# User_Interface.net
KiCad netlist of a schematic drawn in Altium Designer
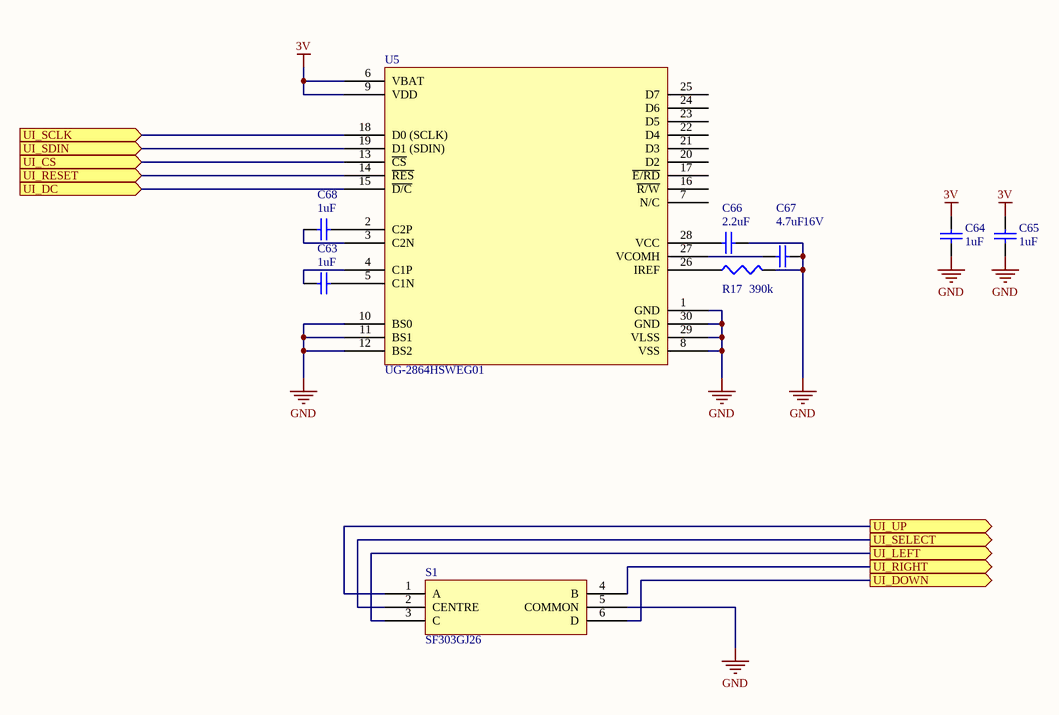
[diagram p0: User_Interface.SchDoc]

(export (version "E")
  (design (tool "Eeschema 10.0.6"))
  (components
    (comp (ref "C63")
      (value "1uF")
      (footprint "1608[0603]")
      (description "Capacitor (Semiconductor SIM Model)")
      (fields (field (name "Comment") "Cap Semi") (field (name "PUBLISHER") "Altium Limited"))
      (libsource (lib "Miscellaneous Devices") (part "Cap Semi"))
    )
    (comp (ref "C64")
      (value "1uF")
      (footprint "1608[0603]")
      (description "Capacitor (Semiconductor SIM Model)")
      (fields (field (name "Comment") "Cap Semi") (field (name "PUBLISHER") "Altium Limited"))
      (libsource (lib "Miscellaneous Devices") (part "Cap Semi"))
    )
    (comp (ref "C65")
      (value "1uF")
      (footprint "1608[0603]")
      (description "Capacitor (Semiconductor SIM Model)")
      (fields (field (name "Comment") "Cap Semi") (field (name "PUBLISHER") "Altium Limited"))
      (libsource (lib "Miscellaneous Devices") (part "Cap Semi"))
    )
    (comp (ref "C66")
      (value "2.2uF")
      (footprint "1608[0603]")
      (description "Capacitor (Semiconductor SIM Model)")
      (fields (field (name "Comment") "Cap Semi") (field (name "PUBLISHER") "Altium Limited"))
      (libsource (lib "Miscellaneous Devices") (part "Cap Semi"))
    )
    (comp (ref "C67")
      (value "4.7uF")
      (footprint "1608[0603]")
      (description "Capacitor (Semiconductor SIM Model)")
      (fields
        (field (name "VOLTAGE") "16V")
        (field (name "Comment") "Cap Semi")
        (field (name "PUBLISHER") "Altium Limited")
      )
      (libsource (lib "Miscellaneous Devices") (part "Cap Semi"))
    )
    (comp (ref "C68")
      (value "1uF")
      (footprint "1608[0603]")
      (description "Capacitor (Semiconductor SIM Model)")
      (fields (field (name "Comment") "Cap Semi") (field (name "PUBLISHER") "Altium Limited"))
      (libsource (lib "Miscellaneous Devices") (part "Cap Semi"))
    )
    (comp (ref "R17")
      (value "390k")
      (footprint "J1-0603")
      (description "Resistor")
      (fields (field (name "Comment") "Res3") (field (name "PUBLISHER") "Altium Limited"))
      (libsource (lib "Miscellaneous Devices") (part "Res3"))
    )
    (comp (ref "S1")
      (value "SF303GJ26")
      (footprint "SF303GJ26")
      (description "5 Way Tactile Switch")
      (libsource (lib "Logic_RF_Component_Symbols") (part "SF303GJ26"))
    )
    (comp (ref "U5")
      (value "UG-2864HSWEG01")
      (footprint "UG-2864HSWEG01")
      (description "128x64 Bi-Colour OLED module")
      (libsource (lib "Logic_RF_Component_Symbols") (part "UG-2864HSWEG01"))
    )
  )
  (nets
    (net (code "1") (name "/UI_CS") (class "Default")
      (node (ref "U5") (pin "13") (pinfunction "~{CS}_13") (pintype "passive"))
    )
    (net (code "2") (name "/UI_DC") (class "Default")
      (node (ref "U5") (pin "15") (pinfunction "~{D/C}_15") (pintype "passive"))
    )
    (net (code "3") (name "/UI_DOWN") (class "Default")
      (node (ref "S1") (pin "6") (pinfunction "D_6") (pintype "passive"))
    )
    (net (code "4") (name "/UI_LEFT") (class "Default")
      (node (ref "S1") (pin "3") (pinfunction "C_3") (pintype "passive"))
    )
    (net (code "5") (name "/UI_RESET") (class "Default")
      (node (ref "U5") (pin "14") (pinfunction "~{RES}_14") (pintype "passive"))
    )
    (net (code "6") (name "/UI_RIGHT") (class "Default")
      (node (ref "S1") (pin "4") (pinfunction "B_4") (pintype "passive"))
    )
    (net (code "7") (name "/UI_SCLK") (class "Default")
      (node (ref "U5") (pin "18") (pinfunction "D0_(SCLK)_18") (pintype "passive"))
    )
    (net (code "8") (name "/UI_SDIN") (class "Default")
      (node (ref "U5") (pin "19") (pinfunction "D1_(SDIN)_19") (pintype "passive"))
    )
    (net (code "9") (name "/UI_SELECT") (class "Default")
      (node (ref "S1") (pin "2") (pinfunction "CENTRE_2") (pintype "passive"))
    )
    (net (code "10") (name "/UI_UP") (class "Default")
      (node (ref "S1") (pin "1") (pinfunction "A_1") (pintype "passive"))
    )
    (net (code "11") (name "3V") (class "Default")
      (node (ref "C64") (pin "2") (pinfunction "2_2") (pintype "passive"))
      (node (ref "C65") (pin "2") (pinfunction "2_2") (pintype "passive"))
      (node (ref "U5") (pin "6") (pinfunction "VBAT_6") (pintype "passive"))
      (node (ref "U5") (pin "9") (pinfunction "VDD_9") (pintype "passive"))
    )
    (net (code "12") (name "GND") (class "Default")
      (node (ref "C64") (pin "1") (pinfunction "1_1") (pintype "passive"))
      (node (ref "C65") (pin "1") (pinfunction "1_1") (pintype "passive"))
      (node (ref "C66") (pin "1") (pinfunction "1_1") (pintype "passive"))
      (node (ref "C67") (pin "1") (pinfunction "1_1") (pintype "passive"))
      (node (ref "R17") (pin "2") (pinfunction "2_2") (pintype "passive"))
      (node (ref "S1") (pin "5") (pinfunction "COMMON_5") (pintype "passive"))
      (node (ref "U5") (pin "1") (pinfunction "GND_1") (pintype "passive"))
      (node (ref "U5") (pin "10") (pinfunction "BS0_10") (pintype "passive"))
      (node (ref "U5") (pin "11") (pinfunction "BS1_11") (pintype "passive"))
      (node (ref "U5") (pin "12") (pinfunction "BS2_12") (pintype "passive"))
      (node (ref "U5") (pin "29") (pinfunction "VLSS_29") (pintype "passive"))
      (node (ref "U5") (pin "30") (pinfunction "GND_30") (pintype "passive"))
      (node (ref "U5") (pin "8") (pinfunction "VSS_8") (pintype "passive"))
    )
    (net (code "13") (name "Net-(U5-C1N)") (class "Default")
      (node (ref "C63") (pin "1") (pinfunction "1_1") (pintype "passive"))
      (node (ref "U5") (pin "5") (pinfunction "C1N_5") (pintype "passive"))
    )
    (net (code "14") (name "Net-(U5-C1P)") (class "Default")
      (node (ref "C63") (pin "2") (pinfunction "2_2") (pintype "passive"))
      (node (ref "U5") (pin "4") (pinfunction "C1P_4") (pintype "passive"))
    )
    (net (code "15") (name "Net-(U5-C2N)") (class "Default")
      (node (ref "C68") (pin "2") (pinfunction "2_2") (pintype "passive"))
      (node (ref "U5") (pin "3") (pinfunction "C2N_3") (pintype "passive"))
    )
    (net (code "16") (name "Net-(U5-C2P)") (class "Default")
      (node (ref "C68") (pin "1") (pinfunction "1_1") (pintype "passive"))
      (node (ref "U5") (pin "2") (pinfunction "C2P_2") (pintype "passive"))
    )
    (net (code "17") (name "Net-(U5-IREF)") (class "Default")
      (node (ref "R17") (pin "1") (pinfunction "1_1") (pintype "passive"))
      (node (ref "U5") (pin "26") (pinfunction "IREF_26") (pintype "passive"))
    )
    (net (code "18") (name "Net-(U5-VCC)") (class "Default")
      (node (ref "C66") (pin "2") (pinfunction "2_2") (pintype "passive"))
      (node (ref "U5") (pin "28") (pinfunction "VCC_28") (pintype "passive"))
    )
    (net (code "19") (name "Net-(U5-VCOMH)") (class "Default")
      (node (ref "C67") (pin "2") (pinfunction "2_2") (pintype "passive"))
      (node (ref "U5") (pin "27") (pinfunction "VCOMH_27") (pintype "passive"))
    )
    (net (code "20") (name "unconnected-(U5-D2-Pad20)") (class "Default")
      (node (ref "U5") (pin "20") (pinfunction "D2_20") (pintype "passive"))
    )
    (net (code "21") (name "unconnected-(U5-D3-Pad21)") (class "Default")
      (node (ref "U5") (pin "21") (pinfunction "D3_21") (pintype "passive"))
    )
    (net (code "22") (name "unconnected-(U5-D4-Pad22)") (class "Default")
      (node (ref "U5") (pin "22") (pinfunction "D4_22") (pintype "passive"))
    )
    (net (code "23") (name "unconnected-(U5-D5-Pad23)") (class "Default")
      (node (ref "U5") (pin "23") (pinfunction "D5_23") (pintype "passive"))
    )
    (net (code "24") (name "unconnected-(U5-D6-Pad24)") (class "Default")
      (node (ref "U5") (pin "24") (pinfunction "D6_24") (pintype "passive"))
    )
    (net (code "25") (name "unconnected-(U5-D7-Pad25)") (class "Default")
      (node (ref "U5") (pin "25") (pinfunction "D7_25") (pintype "passive"))
    )
    (net (code "26") (name "unconnected-(U5-N{slash}C-Pad7)") (class "Default")
      (node (ref "U5") (pin "7") (pinfunction "N/C_7") (pintype "passive"))
    )
    (net (code "27") (name "unconnected-(U5-~{E{slash}RD}-Pad17)") (class "Default")
      (node (ref "U5") (pin "17") (pinfunction "~{E/RD}_17") (pintype "passive"))
    )
    (net (code "28") (name "unconnected-(U5-~{R{slash}W}-Pad16)") (class "Default")
      (node (ref "U5") (pin "16") (pinfunction "~{R/W}_16") (pintype "passive"))
    )
  )
)
